# ProDocument__DCDC_2023-12-31.net
KiCad netlist of a schematic drawn in EasyEDA Pro
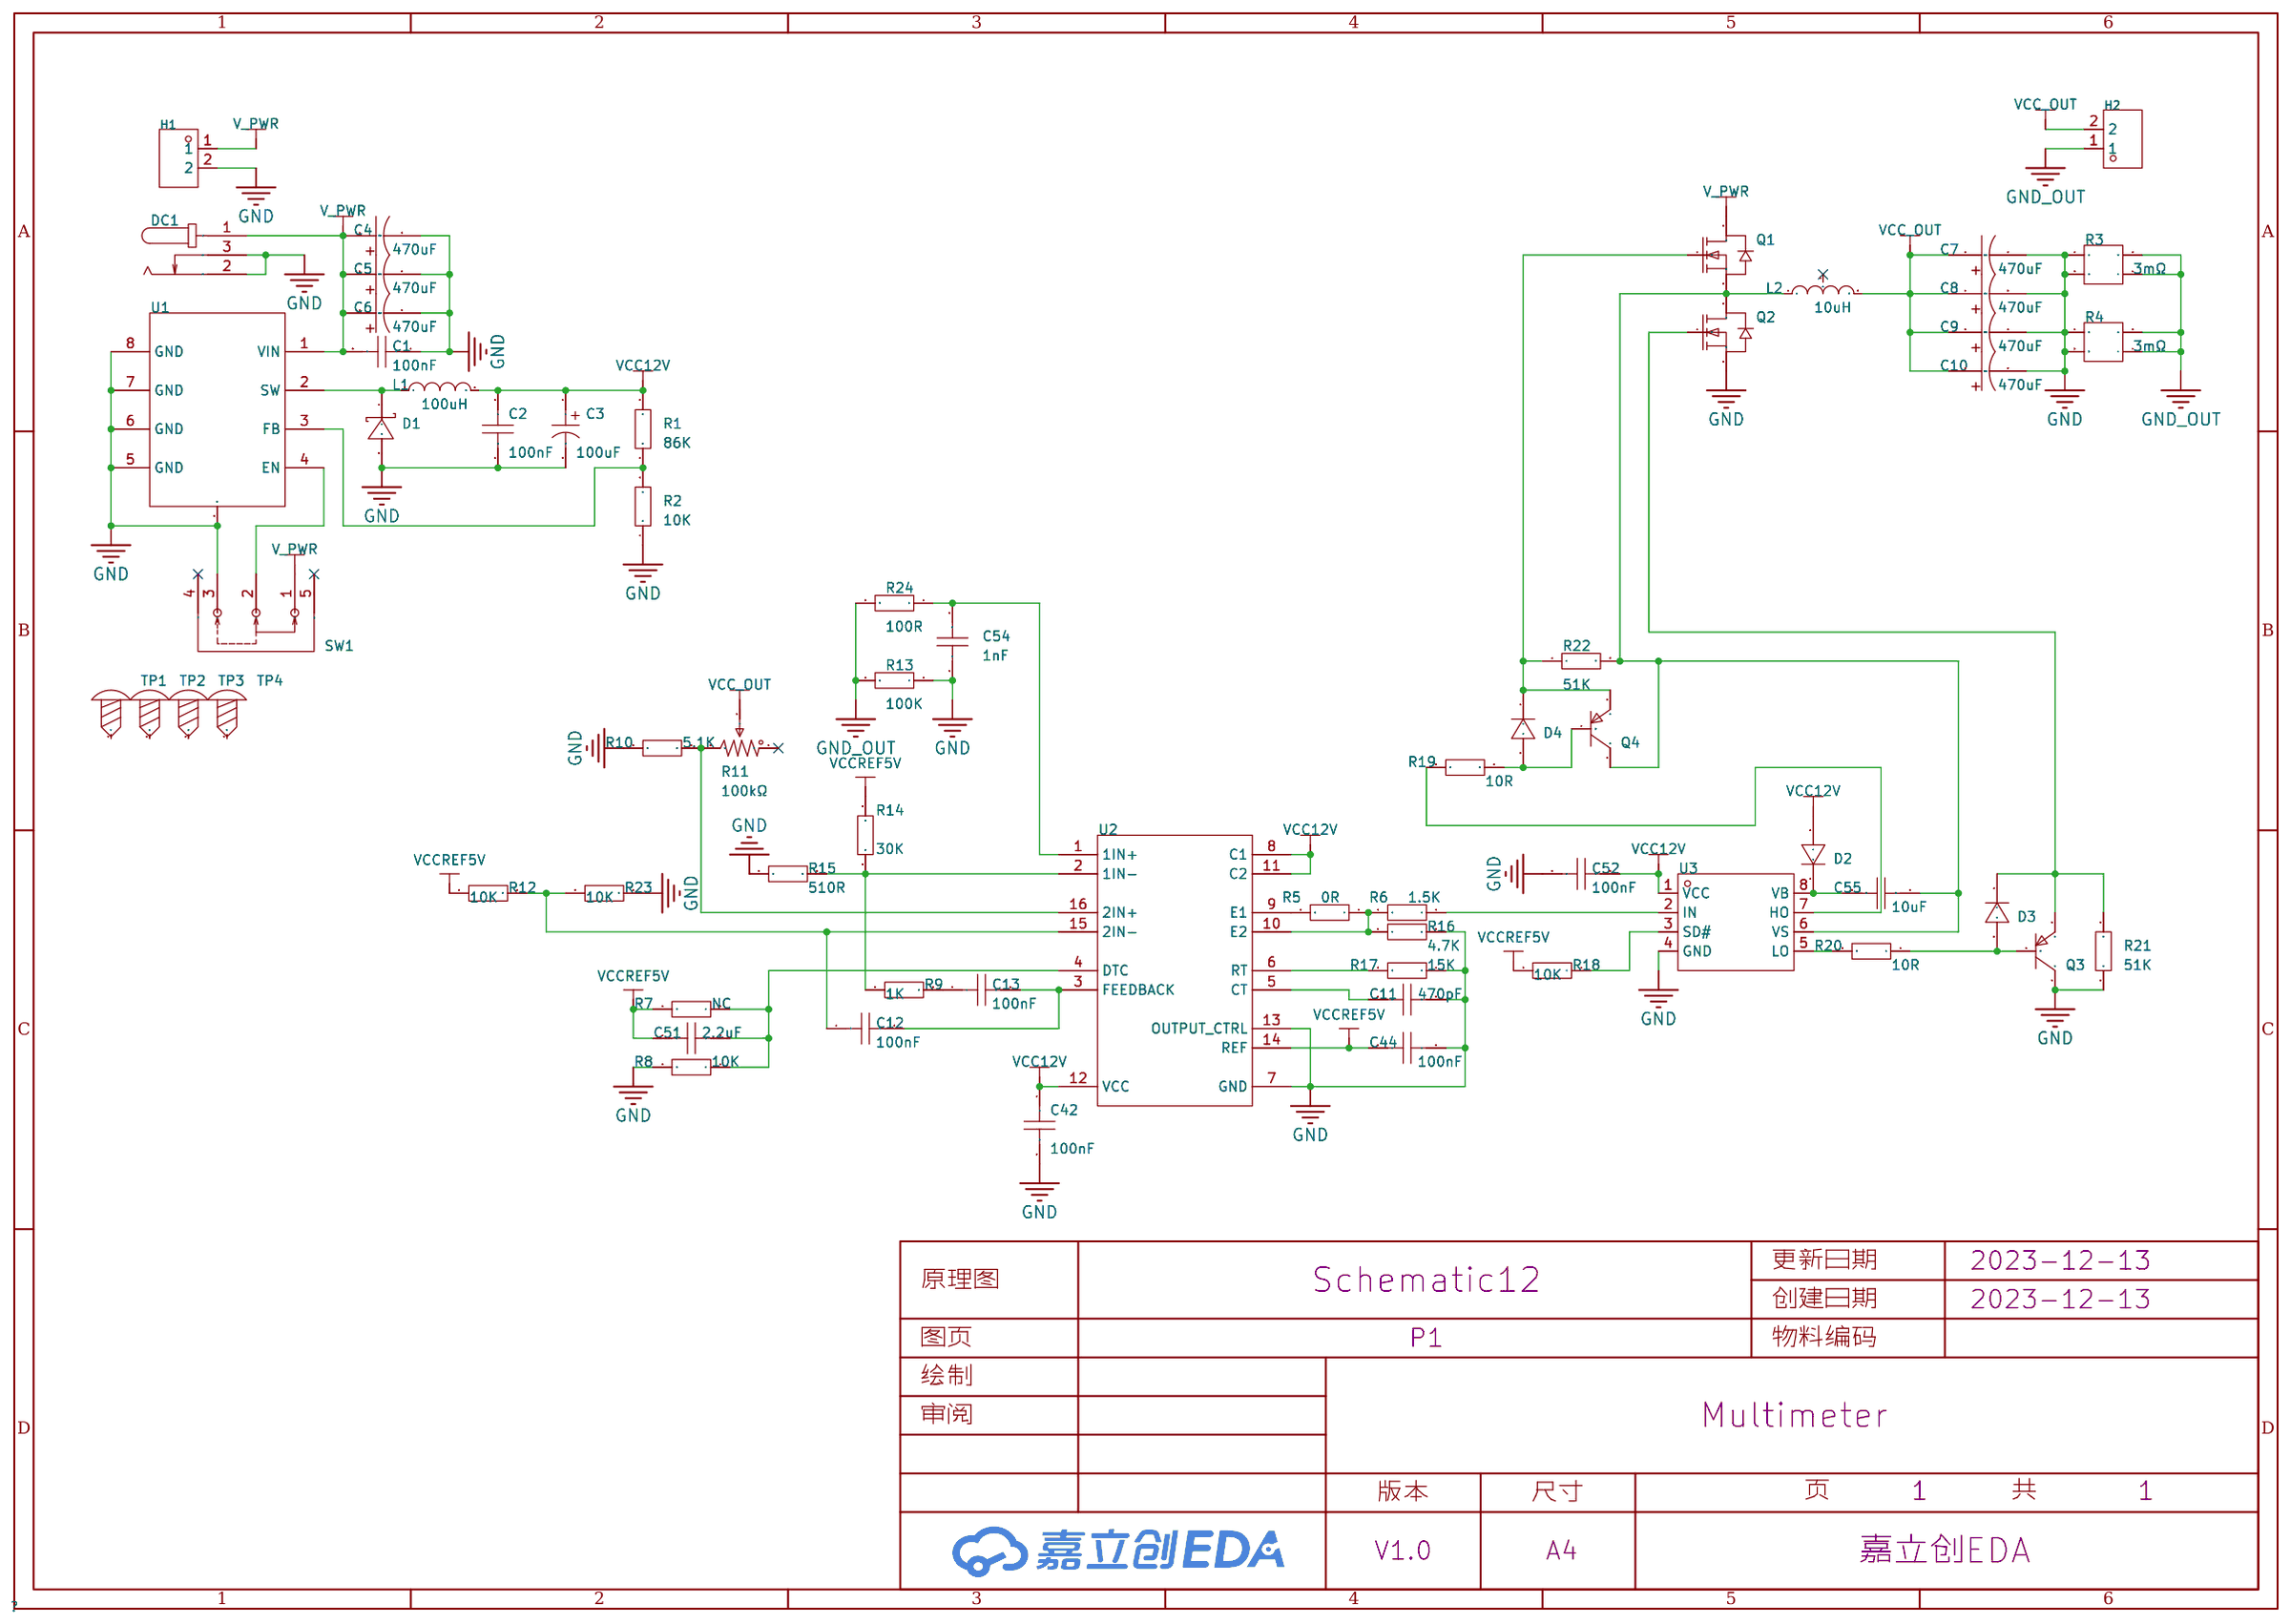
[diagram p0: schematic sheet]

(export (version "E")
  (design (tool "Eeschema 10.0.6"))
  (components
    (comp (ref "C1")
      (value "100nF")
      (footprint "easyedapro:C0603")
      (libsource (lib "easyedapro") (part "CapAcitance"))
    )
    (comp (ref "C2")
      (value "100nF")
      (footprint "easyedapro:C0603")
      (libsource (lib "easyedapro") (part "CapAcitance"))
    )
    (comp (ref "C3")
      (value "100uF")
      (footprint "easyedapro:CAP-SMD_BD6.3-L6.6-W6.6-LS7.6-FD-1")
      (description "容值:100uF;精度:±20%;额定电压:35V;纹波电流:230mA@120Hz;等效串联电阻:600mΩ@100kHz;")
      (fields
        (field (name "Manufacturer Part") "RVE100UF35V67RV0072")
        (field (name "Manufacturer") "KNSCHA(科尼盛)")
      )
      (libsource (lib "easyedapro") (part "RVE100UF35V67RV0072"))
    )
    (comp (ref "C4")
      (value "470uF")
      (footprint "easyedapro:CAP-TH_BD16.0-P7.50-D1.2-FD")
      (description "容值:470uF;精度:±20%;额定电压:100V;纹波电流:-;等效串联电阻:-;")
      (fields (field (name "Manufacturer Part") "ERE1KM471L25OT") (field (name "Manufacturer") "AISHI(艾华集团)"))
      (libsource (lib "easyedapro") (part "ERE1KM471L25OT"))
    )
    (comp (ref "C5")
      (value "470uF")
      (footprint "easyedapro:CAP-TH_BD16.0-P7.50-D1.2-FD")
      (description "容值:470uF;精度:±20%;额定电压:100V;纹波电流:-;等效串联电阻:-;")
      (fields (field (name "Manufacturer Part") "ERE1KM471L25OT") (field (name "Manufacturer") "AISHI(艾华集团)"))
      (libsource (lib "easyedapro") (part "ERE1KM471L25OT"))
    )
    (comp (ref "C6")
      (value "470uF")
      (footprint "easyedapro:CAP-TH_BD16.0-P7.50-D1.2-FD")
      (description "容值:470uF;精度:±20%;额定电压:100V;纹波电流:-;等效串联电阻:-;")
      (fields (field (name "Manufacturer Part") "ERE1KM471L25OT") (field (name "Manufacturer") "AISHI(艾华集团)"))
      (libsource (lib "easyedapro") (part "ERE1KM471L25OT"))
    )
    (comp (ref "C7")
      (value "470uF")
      (footprint "easyedapro:CAP-TH_BD16.0-P7.50-D1.2-FD")
      (description "容值:470uF;精度:±20%;额定电压:100V;纹波电流:-;等效串联电阻:-;")
      (fields (field (name "Manufacturer Part") "ERE1KM471L25OT") (field (name "Manufacturer") "AISHI(艾华集团)"))
      (libsource (lib "easyedapro") (part "ERE1KM471L25OT"))
    )
    (comp (ref "C8")
      (value "470uF")
      (footprint "easyedapro:CAP-TH_BD16.0-P7.50-D1.2-FD")
      (description "容值:470uF;精度:±20%;额定电压:100V;纹波电流:-;等效串联电阻:-;")
      (fields (field (name "Manufacturer Part") "ERE1KM471L25OT") (field (name "Manufacturer") "AISHI(艾华集团)"))
      (libsource (lib "easyedapro") (part "ERE1KM471L25OT"))
    )
    (comp (ref "C9")
      (value "470uF")
      (footprint "easyedapro:CAP-TH_BD16.0-P7.50-D1.2-FD")
      (description "容值:470uF;精度:±20%;额定电压:100V;纹波电流:-;等效串联电阻:-;")
      (fields (field (name "Manufacturer Part") "ERE1KM471L25OT") (field (name "Manufacturer") "AISHI(艾华集团)"))
      (libsource (lib "easyedapro") (part "ERE1KM471L25OT"))
    )
    (comp (ref "C10")
      (value "470uF")
      (footprint "easyedapro:CAP-TH_BD16.0-P7.50-D1.2-FD")
      (description "容值:470uF;精度:±20%;额定电压:100V;纹波电流:-;等效串联电阻:-;")
      (fields (field (name "Manufacturer Part") "ERE1KM471L25OT") (field (name "Manufacturer") "AISHI(艾华集团)"))
      (libsource (lib "easyedapro") (part "ERE1KM471L25OT"))
    )
    (comp (ref "C11")
      (value "470pF")
      (footprint "easyedapro:C0603")
      (libsource (lib "easyedapro") (part "CapAcitance"))
    )
    (comp (ref "C12")
      (value "100nF")
      (footprint "easyedapro:C0603")
      (libsource (lib "easyedapro") (part "CapAcitance"))
    )
    (comp (ref "C13")
      (value "100nF")
      (footprint "easyedapro:C0603")
      (libsource (lib "easyedapro") (part "CapAcitance"))
    )
    (comp (ref "C42")
      (value "100nF")
      (footprint "easyedapro:C0603")
      (libsource (lib "easyedapro") (part "CapAcitance"))
    )
    (comp (ref "C44")
      (value "100nF")
      (footprint "easyedapro:C0603")
      (libsource (lib "easyedapro") (part "CapAcitance"))
    )
    (comp (ref "C51")
      (value "2.2uF")
      (footprint "easyedapro:C0603")
      (libsource (lib "easyedapro") (part "CapAcitance"))
    )
    (comp (ref "C52")
      (value "100nF")
      (footprint "easyedapro:C0603")
      (libsource (lib "easyedapro") (part "CapAcitance"))
    )
    (comp (ref "C54")
      (value "1nF")
      (footprint "easyedapro:C0603")
      (libsource (lib "easyedapro") (part "CapAcitance"))
    )
    (comp (ref "C55")
      (value "10uF")
      (footprint "easyedapro:C0603")
      (description "容值:100nF;精度:±10%;额定电压:50V;材质(温度系数):X7R;")
      (fields
        (field (name "Manufacturer Part") "CC0603KRX7R9BB104")
        (field (name "Manufacturer") "YAGEO(国巨)")
      )
      (libsource (lib "easyedapro") (part "CC0603KRX7R9BB104"))
    )
    (comp (ref "D1")
      (value "SS210")
      (footprint "easyedapro:SMA_L4.3-W2.6-LS5.2-RD")
      (description "直流反向耐压(Vr):100V;平均整流电流(Io):2A;正向压降(Vf):850mV@2A;")
      (fields (field (name "Manufacturer") "MDD"))
      (libsource (lib "easyedapro") (part "SS210"))
    )
    (comp (ref "D2")
      (value "1N4148W")
      (footprint "easyedapro:SOD-123_L2.8-W1.8-LS3.7-RD")
      (fields (field (name "Manufacturer") "CJ(江苏长电/长晶)"))
      (libsource (lib "easyedapro") (part "1N4148W T4"))
    )
    (comp (ref "D3")
      (value "1N4148W")
      (footprint "easyedapro:SOD-123_L2.8-W1.8-LS3.7-RD")
      (fields (field (name "Manufacturer") "CJ(江苏长电/长晶)"))
      (libsource (lib "easyedapro") (part "1N4148W T4"))
    )
    (comp (ref "D4")
      (value "1N4148W")
      (footprint "easyedapro:SOD-123_L2.8-W1.8-LS3.7-RD")
      (fields (field (name "Manufacturer") "CJ(江苏长电/长晶)"))
      (libsource (lib "easyedapro") (part "1N4148W T4"))
    )
    (comp (ref "DC1")
      (value "DC-005-20A")
      (footprint "easyedapro:DC-IN-TH_DC-005-20A")
      (description "触点内径:2mm;触点外径:6.4mm;额定电流:500mA;额定电压:30V;")
      (fields (field (name "Manufacturer") "韩国韩荣"))
      (libsource (lib "easyedapro") (part "DC-005-20A_C136744"))
    )
    (comp (ref "H1")
      (value "DBT50G-9.5-2P")
      (footprint "easyedapro:CONN-TH_2P-P9.50_DBT50G-9.5-2P")
      (fields (field (name "Manufacturer") "DIBO(地博电气)"))
      (libsource (lib "easyedapro") (part "DBT50G-9.5-2P"))
    )
    (comp (ref "H2")
      (value "DBT50G-9.5-2P")
      (footprint "easyedapro:CONN-TH_2P-P9.50_DBT50G-9.5-2P")
      (fields (field (name "Manufacturer") "DIBO(地博电气)"))
      (libsource (lib "easyedapro") (part "DBT50G-9.5-2P"))
    )
    (comp (ref "L1")
      (value "100uH")
      (footprint "easyedapro:IND-SMD_L7.1-W6.6")
      (description "电感值:100uH;精度:±20%;额定电流:1.5A;饱和电流(Isat):2A;")
      (fields (field (name "Manufacturer Part") "SMMS0650-101M") (field (name "Manufacturer") "SXN(顺翔诺)"))
      (libsource (lib "easyedapro") (part "SMMS0650-101M"))
    )
    (comp (ref "L2")
      (value "10uH")
      (footprint "easyedapro:IND-SMD_3P-L27.9-W19.7-P10.43-LS27.9-BL-A")
      (description "电感值:10uH;精度:±20%;额定电流:30A;类型:-;饱和电流(Isat):32.1A;")
      (fields (field (name "Manufacturer Part") "FC-SE2918-100M-28A") (field (name "Manufacturer") "FC(方成)"))
      (libsource (lib "easyedapro") (part "FC-SE2918-100M-28A"))
    )
    (comp (ref "Q1")
      (value "NCEP01T18T")
      (footprint "easyedapro:PG-TO247-3_L15.9-W5.2-P5.44-L")
      (fields (field (name "Manufacturer") "NCE(无锡新洁能)"))
      (libsource (lib "easyedapro") (part "NCEP01T18T"))
    )
    (comp (ref "Q2")
      (value "NCEP01T18T")
      (footprint "easyedapro:PG-TO247-3_L15.9-W5.2-P5.44-L")
      (fields (field (name "Manufacturer") "NCE(无锡新洁能)"))
      (libsource (lib "easyedapro") (part "NCEP01T18T"))
    )
    (comp (ref "Q3")
      (value "SS8550 Y2")
      (footprint "easyedapro:SOT-23-3_L2.9-W1.3-P1.90-LS2.4-BR")
      (description "晶体管类型:PNP;集电极电流(Ic):1.5A;集射极击穿电压(Vceo):25V;功率(Pd):300mW;直流电流增益(hFE@Ic,Vce):200@100mA,1V;")
      (fields (field (name "Manufacturer") "CJ(江苏长电/长晶)"))
      (libsource (lib "easyedapro") (part "SS8550_C8542"))
    )
    (comp (ref "Q4")
      (value "SS8550 Y2")
      (footprint "easyedapro:SOT-23-3_L2.9-W1.3-P1.90-LS2.4-BR")
      (description "晶体管类型:PNP;集电极电流(Ic):1.5A;集射极击穿电压(Vceo):25V;功率(Pd):300mW;直流电流增益(hFE@Ic,Vce):200@100mA,1V;")
      (fields (field (name "Manufacturer") "CJ(江苏长电/长晶)"))
      (libsource (lib "easyedapro") (part "SS8550_C8542"))
    )
    (comp (ref "R1") (value "86K") (footprint "easyedapro:R0603") (libsource (lib "easyedapro") (part "电阻")))
    (comp (ref "R2") (value "10K") (footprint "easyedapro:R0603") (libsource (lib "easyedapro") (part "电阻")))
    (comp (ref "R3")
      (value "3mΩ")
      (footprint "easyedapro:RES-TH_4P-L8.3-W5.3-P3.10-BL")
      (description "阻值:3mΩ;精度:±1%;功率:5W;")
      (fields
        (field (name "Manufacturer Part") "HOBH3820-5W-3mR-1%")
        (field (name "Manufacturer") "Milliohm(毫欧)")
      )
      (libsource (lib "easyedapro") (part "HOBH3820-5W-3MR-1%"))
    )
    (comp (ref "R4")
      (value "3mΩ")
      (footprint "easyedapro:RES-TH_4P-L8.3-W5.3-P3.10-BL")
      (description "阻值:3mΩ;精度:±1%;功率:5W;")
      (fields
        (field (name "Manufacturer Part") "HOBH3820-5W-3mR-1%")
        (field (name "Manufacturer") "Milliohm(毫欧)")
      )
      (libsource (lib "easyedapro") (part "HOBH3820-5W-3MR-1%"))
    )
    (comp (ref "R5") (value "0R") (footprint "easyedapro:R0603") (libsource (lib "easyedapro") (part "电阻")))
    (comp (ref "R6") (value "1.5K") (footprint "easyedapro:R0603") (libsource (lib "easyedapro") (part "电阻")))
    (comp (ref "R7") (value "NC") (footprint "easyedapro:R0603") (libsource (lib "easyedapro") (part "电阻")))
    (comp (ref "R8") (value "10K") (footprint "easyedapro:R0603") (libsource (lib "easyedapro") (part "电阻")))
    (comp (ref "R9") (value "1K") (footprint "easyedapro:R0603") (libsource (lib "easyedapro") (part "电阻")))
    (comp (ref "R10")
      (value "5.1K")
      (footprint "easyedapro:R0603")
      (libsource (lib "easyedapro") (part "电阻"))
    )
    (comp (ref "R11")
      (value "100kΩ")
      (footprint "easyedapro:RES-ADJ-TH_3362P")
      (description "阻值:100kΩ;精度:±10%;")
      (fields (field (name "Manufacturer Part") "3362P-1-104") (field (name "Manufacturer") "BOCHEN(博晨)"))
      (libsource (lib "easyedapro") (part "3362P-1-104_C118966"))
    )
    (comp (ref "R12") (value "10K") (footprint "easyedapro:R0603") (libsource (lib "easyedapro") (part "电阻")))
    (comp (ref "R13")
      (value "100K")
      (footprint "easyedapro:R0603")
      (libsource (lib "easyedapro") (part "电阻"))
    )
    (comp (ref "R14") (value "30K") (footprint "easyedapro:R0603") (libsource (lib "easyedapro") (part "电阻")))
    (comp (ref "R15")
      (value "510R")
      (footprint "easyedapro:R0603")
      (libsource (lib "easyedapro") (part "电阻"))
    )
    (comp (ref "R16")
      (value "4.7K")
      (footprint "easyedapro:R0603")
      (libsource (lib "easyedapro") (part "电阻"))
    )
    (comp (ref "R17") (value "15K") (footprint "easyedapro:R0603") (libsource (lib "easyedapro") (part "电阻")))
    (comp (ref "R18") (value "10K") (footprint "easyedapro:R0603") (libsource (lib "easyedapro") (part "电阻")))
    (comp (ref "R19") (value "10R") (footprint "easyedapro:R0603") (libsource (lib "easyedapro") (part "电阻")))
    (comp (ref "R20") (value "10R") (footprint "easyedapro:R0603") (libsource (lib "easyedapro") (part "电阻")))
    (comp (ref "R21") (value "51K") (footprint "easyedapro:R0603") (libsource (lib "easyedapro") (part "电阻")))
    (comp (ref "R22") (value "51K") (footprint "easyedapro:R0603") (libsource (lib "easyedapro") (part "电阻")))
    (comp (ref "R23") (value "10K") (footprint "easyedapro:R0603") (libsource (lib "easyedapro") (part "电阻")))
    (comp (ref "R24")
      (value "100R")
      (footprint "easyedapro:R0603")
      (libsource (lib "easyedapro") (part "电阻"))
    )
    (comp (ref "SW1")
      (value "SK12D07VG4")
      (footprint "easyedapro:SW-TH_SK12D07VG4")
      (description "电路结构:单刀双掷;安装方式:卧插;额定电流(DC):500mA;额定电压(DC):50V;额定电流(AC):-;额定电压(AC):-;机械寿命:5千次;")
      (fields (field (name "Manufacturer") "SHOU HAN(首韩)"))
      (libsource (lib "easyedapro") (part "SK12D07VG4"))
    )
    (comp (ref "TP1") (value "~") (footprint "easyedapro:M3螺丝") (libsource (lib "easyedapro") (part "螺丝孔")))
    (comp (ref "TP2") (value "~") (footprint "easyedapro:M3螺丝") (libsource (lib "easyedapro") (part "螺丝孔")))
    (comp (ref "TP3") (value "~") (footprint "easyedapro:M3螺丝") (libsource (lib "easyedapro") (part "螺丝孔")))
    (comp (ref "TP4") (value "~") (footprint "easyedapro:M3螺丝") (libsource (lib "easyedapro") (part "螺丝孔")))
    (comp (ref "U1")
      (value "XL7005A")
      (footprint "easyedapro:SOIC-8_L4.9-W3.9-P1.27-LS6.0-BL-EP3.1-1")
      (description "功能类型:降压型;同步整流:-;输出通道数:-;拓扑结构:-;输入电压:-;输出电流(最大值):-;开关频率:-;")
      (fields (field (name "Manufacturer") "XLSEMI(芯龙)"))
      (libsource (lib "easyedapro") (part "XL7005A"))
    )
    (comp (ref "U2")
      (value "TL494CDR")
      (footprint "easyedapro:SOIC-16_L9.9-W3.9-P1.27-LS6.0-BL")
      (description "TL494 脉冲宽度调制 (Pwm) 控制电路")
      (fields (field (name "Manufacturer") "TI(德州仪器)"))
      (libsource (lib "easyedapro") (part "TL494CDR"))
    )
    (comp (ref "U3")
      (value "EG2104")
      (footprint "easyedapro:SOP-8_L5.0-W4.0-P1.27-LS6.2-BL")
      (description "高性价比, 600V，半桥式Nmos预驱动器")
      (fields (field (name "Manufacturer") "EG(屹晶微)"))
      (libsource (lib "easyedapro") (part "EG2104"))
    )
  )
  (nets
    (net (code "1") (name "GND") (class "Default")
      (node (ref "C1") (pin "1") (pinfunction "1_1") (pintype "input"))
      (node (ref "C10") (pin "2") (pinfunction "2_2") (pintype "input"))
      (node (ref "C11") (pin "2") (pinfunction "2_2") (pintype "input"))
      (node (ref "C2") (pin "1") (pinfunction "1_1") (pintype "input"))
      (node (ref "C3") (pin "2") (pinfunction "2_2") (pintype "input"))
      (node (ref "C4") (pin "2") (pinfunction "2_2") (pintype "input"))
      (node (ref "C42") (pin "2") (pinfunction "2_2") (pintype "input"))
      (node (ref "C44") (pin "2") (pinfunction "2_2") (pintype "input"))
      (node (ref "C5") (pin "2") (pinfunction "2_2") (pintype "input"))
      (node (ref "C52") (pin "1") (pinfunction "1_1") (pintype "input"))
      (node (ref "C54") (pin "1") (pinfunction "1_1") (pintype "input"))
      (node (ref "C6") (pin "2") (pinfunction "2_2") (pintype "input"))
      (node (ref "C7") (pin "2") (pinfunction "2_2") (pintype "input"))
      (node (ref "C8") (pin "2") (pinfunction "2_2") (pintype "input"))
      (node (ref "C9") (pin "2") (pinfunction "2_2") (pintype "input"))
      (node (ref "D1") (pin "2") (pinfunction "A_2") (pintype "input"))
      (node (ref "DC1") (pin "2") (pinfunction "2_2") (pintype "input"))
      (node (ref "DC1") (pin "3") (pinfunction "3_3") (pintype "input"))
      (node (ref "H1") (pin "2") (pinfunction "2_2") (pintype "input"))
      (node (ref "Q2") (pin "3") (pinfunction "S_3") (pintype "input"))
      (node (ref "Q3") (pin "3") (pinfunction "C_3") (pintype "unspecified"))
      (node (ref "R10") (pin "2") (pinfunction "2_2") (pintype "input"))
      (node (ref "R13") (pin "1") (pinfunction "1_1") (pintype "input"))
      (node (ref "R15") (pin "2") (pinfunction "2_2") (pintype "input"))
      (node (ref "R16") (pin "1") (pinfunction "1_1") (pintype "input"))
      (node (ref "R17") (pin "1") (pinfunction "1_1") (pintype "input"))
      (node (ref "R2") (pin "1") (pinfunction "1_1") (pintype "input"))
      (node (ref "R21") (pin "2") (pinfunction "2_2") (pintype "input"))
      (node (ref "R23") (pin "1") (pinfunction "1_1") (pintype "input"))
      (node (ref "R3") (pin "1") (pinfunction "1_1") (pintype "input"))
      (node (ref "R3") (pin "3") (pinfunction "3_3") (pintype "input"))
      (node (ref "R4") (pin "1") (pinfunction "1_1") (pintype "input"))
      (node (ref "R4") (pin "3") (pinfunction "3_3") (pintype "input"))
      (node (ref "R8") (pin "2") (pinfunction "2_2") (pintype "input"))
      (node (ref "SW1") (pin "3") (pinfunction "3_3") (pintype "unspecified"))
      (node (ref "U1") (pin "5") (pinfunction "GND_5") (pintype "input"))
      (node (ref "U1") (pin "6") (pinfunction "GND_6") (pintype "input"))
      (node (ref "U1") (pin "7") (pinfunction "GND_7") (pintype "input"))
      (node (ref "U1") (pin "8") (pinfunction "GND_8") (pintype "input"))
      (node (ref "U1") (pin "9") (pinfunction "9_9") (pintype "input"))
      (node (ref "U2") (pin "13") (pinfunction "OUTPUT_CTRL_13") (pintype "input"))
      (node (ref "U2") (pin "7") (pinfunction "GND_7") (pintype "input"))
      (node (ref "U3") (pin "4") (pinfunction "GND_4") (pintype "unspecified"))
    )
    (net (code "2") (name "GND_OUT") (class "Default")
      (node (ref "H2") (pin "1") (pinfunction "1_1") (pintype "input"))
      (node (ref "R13") (pin "2") (pinfunction "2_2") (pintype "input"))
      (node (ref "R24") (pin "2") (pinfunction "2_2") (pintype "input"))
      (node (ref "R3") (pin "2") (pinfunction "2_2") (pintype "input"))
      (node (ref "R3") (pin "4") (pinfunction "4_4") (pintype "input"))
      (node (ref "R4") (pin "2") (pinfunction "2_2") (pintype "input"))
      (node (ref "R4") (pin "4") (pinfunction "4_4") (pintype "input"))
    )
    (net (code "3") (name "Net-(C13-Pad1)") (class "Default")
      (node (ref "C13") (pin "1") (pinfunction "1_1") (pintype "input"))
      (node (ref "R9") (pin "1") (pinfunction "1_1") (pintype "input"))
    )
    (net (code "4") (name "Net-(D1-K)") (class "Default")
      (node (ref "D1") (pin "1") (pinfunction "K_1") (pintype "input"))
      (node (ref "L1") (pin "1") (pinfunction "1_1") (pintype "input"))
      (node (ref "U1") (pin "2") (pinfunction "SW_2") (pintype "input"))
    )
    (net (code "5") (name "Net-(D2-K)") (class "Default")
      (node (ref "C55") (pin "2") (pinfunction "2_2") (pintype "input"))
      (node (ref "D2") (pin "1") (pinfunction "K_1") (pintype "input"))
      (node (ref "U3") (pin "8") (pinfunction "VB_8") (pintype "unspecified"))
    )
    (net (code "6") (name "Net-(D3-A)") (class "Default")
      (node (ref "D3") (pin "2") (pinfunction "A_2") (pintype "input"))
      (node (ref "Q3") (pin "1") (pinfunction "B_1") (pintype "unspecified"))
      (node (ref "R20") (pin "1") (pinfunction "1_1") (pintype "input"))
    )
    (net (code "7") (name "Net-(D3-K)") (class "Default")
      (node (ref "D3") (pin "1") (pinfunction "K_1") (pintype "input"))
      (node (ref "Q2") (pin "1") (pinfunction "G_1") (pintype "input"))
      (node (ref "Q3") (pin "2") (pinfunction "E_2") (pintype "unspecified"))
      (node (ref "R21") (pin "1") (pinfunction "1_1") (pintype "input"))
    )
    (net (code "8") (name "Net-(D4-A)") (class "Default")
      (node (ref "D4") (pin "2") (pinfunction "A_2") (pintype "input"))
      (node (ref "Q4") (pin "1") (pinfunction "B_1") (pintype "unspecified"))
      (node (ref "R19") (pin "1") (pinfunction "1_1") (pintype "input"))
    )
    (net (code "9") (name "Net-(D4-K)") (class "Default")
      (node (ref "D4") (pin "1") (pinfunction "K_1") (pintype "input"))
      (node (ref "Q1") (pin "1") (pinfunction "G_1") (pintype "input"))
      (node (ref "Q4") (pin "2") (pinfunction "E_2") (pintype "unspecified"))
      (node (ref "R22") (pin "1") (pinfunction "1_1") (pintype "input"))
    )
    (net (code "10") (name "Net-(Q1-S)") (class "Default")
      (node (ref "C55") (pin "1") (pinfunction "1_1") (pintype "input"))
      (node (ref "L2") (pin "1") (pinfunction "1_1") (pintype "unspecified"))
      (node (ref "Q1") (pin "3") (pinfunction "S_3") (pintype "input"))
      (node (ref "Q2") (pin "2") (pinfunction "D_2") (pintype "input"))
      (node (ref "Q4") (pin "3") (pinfunction "C_3") (pintype "unspecified"))
      (node (ref "R22") (pin "2") (pinfunction "2_2") (pintype "input"))
      (node (ref "U3") (pin "6") (pinfunction "VS_6") (pintype "unspecified"))
    )
    (net (code "11") (name "Net-(U1-EN)") (class "Default")
      (node (ref "SW1") (pin "2") (pinfunction "2_2") (pintype "unspecified"))
      (node (ref "U1") (pin "4") (pinfunction "EN_4") (pintype "input"))
    )
    (net (code "12") (name "Net-(U1-FB)") (class "Default")
      (node (ref "R1") (pin "1") (pinfunction "1_1") (pintype "input"))
      (node (ref "R2") (pin "2") (pinfunction "2_2") (pintype "input"))
      (node (ref "U1") (pin "3") (pinfunction "FB_3") (pintype "input"))
    )
    (net (code "13") (name "Net-(U2-1IN+)") (class "Default")
      (node (ref "C54") (pin "2") (pinfunction "2_2") (pintype "input"))
      (node (ref "R24") (pin "1") (pinfunction "1_1") (pintype "input"))
      (node (ref "U2") (pin "1") (pinfunction "1IN+_1") (pintype "input"))
    )
    (net (code "14") (name "Net-(U2-1IN-)") (class "Default")
      (node (ref "R14") (pin "2") (pinfunction "2_2") (pintype "input"))
      (node (ref "R15") (pin "1") (pinfunction "1_1") (pintype "input"))
      (node (ref "R9") (pin "2") (pinfunction "2_2") (pintype "input"))
      (node (ref "U2") (pin "2") (pinfunction "1IN-_2") (pintype "input"))
    )
    (net (code "15") (name "Net-(U2-2IN+)") (class "Default")
      (node (ref "R10") (pin "1") (pinfunction "1_1") (pintype "input"))
      (node (ref "R11") (pin "3") (pinfunction "3_3") (pintype "input"))
      (node (ref "U2") (pin "16") (pinfunction "2IN+_16") (pintype "input"))
    )
    (net (code "16") (name "Net-(U2-2IN-)") (class "Default")
      (node (ref "C12") (pin "1") (pinfunction "1_1") (pintype "input"))
      (node (ref "R12") (pin "1") (pinfunction "1_1") (pintype "input"))
      (node (ref "R23") (pin "2") (pinfunction "2_2") (pintype "input"))
      (node (ref "U2") (pin "15") (pinfunction "2IN-_15") (pintype "input"))
    )
    (net (code "17") (name "Net-(U2-CT)") (class "Default")
      (node (ref "C11") (pin "1") (pinfunction "1_1") (pintype "input"))
      (node (ref "U2") (pin "5") (pinfunction "CT_5") (pintype "input"))
    )
    (net (code "18") (name "Net-(U2-DTC)") (class "Default")
      (node (ref "C51") (pin "2") (pinfunction "2_2") (pintype "input"))
      (node (ref "R7") (pin "1") (pinfunction "1_1") (pintype "input"))
      (node (ref "R8") (pin "1") (pinfunction "1_1") (pintype "input"))
      (node (ref "U2") (pin "4") (pinfunction "DTC_4") (pintype "input"))
    )
    (net (code "19") (name "Net-(U2-E1)") (class "Default")
      (node (ref "R5") (pin "2") (pinfunction "2_2") (pintype "input"))
      (node (ref "U2") (pin "9") (pinfunction "E1_9") (pintype "input"))
    )
    (net (code "20") (name "Net-(U2-E2)") (class "Default")
      (node (ref "R16") (pin "2") (pinfunction "2_2") (pintype "input"))
      (node (ref "R5") (pin "1") (pinfunction "1_1") (pintype "input"))
      (node (ref "R6") (pin "2") (pinfunction "2_2") (pintype "input"))
      (node (ref "U2") (pin "10") (pinfunction "E2_10") (pintype "input"))
    )
    (net (code "21") (name "Net-(U2-FEEDBACK)") (class "Default")
      (node (ref "C12") (pin "2") (pinfunction "2_2") (pintype "input"))
      (node (ref "C13") (pin "2") (pinfunction "2_2") (pintype "input"))
      (node (ref "U2") (pin "3") (pinfunction "FEEDBACK_3") (pintype "input"))
    )
    (net (code "22") (name "Net-(U2-RT)") (class "Default")
      (node (ref "R17") (pin "2") (pinfunction "2_2") (pintype "input"))
      (node (ref "U2") (pin "6") (pinfunction "RT_6") (pintype "input"))
    )
    (net (code "23") (name "Net-(U3-HO)") (class "Default")
      (node (ref "R19") (pin "2") (pinfunction "2_2") (pintype "input"))
      (node (ref "U3") (pin "7") (pinfunction "HO_7") (pintype "unspecified"))
    )
    (net (code "24") (name "Net-(U3-IN)") (class "Default")
      (node (ref "R6") (pin "1") (pinfunction "1_1") (pintype "input"))
      (node (ref "U3") (pin "2") (pinfunction "IN_2") (pintype "unspecified"))
    )
    (net (code "25") (name "Net-(U3-LO)") (class "Default")
      (node (ref "R20") (pin "2") (pinfunction "2_2") (pintype "input"))
      (node (ref "U3") (pin "5") (pinfunction "LO_5") (pintype "unspecified"))
    )
    (net (code "26") (name "Net-(U3-SD#)") (class "Default")
      (node (ref "R18") (pin "1") (pinfunction "1_1") (pintype "input"))
      (node (ref "U3") (pin "3") (pinfunction "SD#_3") (pintype "unspecified"))
    )
    (net (code "27") (name "VCC12V") (class "Default")
      (node (ref "C2") (pin "2") (pinfunction "2_2") (pintype "input"))
      (node (ref "C3") (pin "1") (pinfunction "1_1") (pintype "input"))
      (node (ref "C42") (pin "1") (pinfunction "1_1") (pintype "input"))
      (node (ref "C52") (pin "2") (pinfunction "2_2") (pintype "input"))
      (node (ref "D2") (pin "2") (pinfunction "A_2") (pintype "input"))
      (node (ref "L1") (pin "2") (pinfunction "2_2") (pintype "input"))
      (node (ref "R1") (pin "2") (pinfunction "2_2") (pintype "input"))
      (node (ref "U2") (pin "11") (pinfunction "C2_11") (pintype "input"))
      (node (ref "U2") (pin "12") (pinfunction "VCC_12") (pintype "input"))
      (node (ref "U2") (pin "8") (pinfunction "C1_8") (pintype "input"))
      (node (ref "U3") (pin "1") (pinfunction "VCC_1") (pintype "unspecified"))
    )
    (net (code "28") (name "VCCREF5V") (class "Default")
      (node (ref "C44") (pin "1") (pinfunction "1_1") (pintype "input"))
      (node (ref "C51") (pin "1") (pinfunction "1_1") (pintype "input"))
      (node (ref "R12") (pin "2") (pinfunction "2_2") (pintype "input"))
      (node (ref "R14") (pin "1") (pinfunction "1_1") (pintype "input"))
      (node (ref "R18") (pin "2") (pinfunction "2_2") (pintype "input"))
      (node (ref "R7") (pin "2") (pinfunction "2_2") (pintype "input"))
      (node (ref "U2") (pin "14") (pinfunction "REF_14") (pintype "output"))
    )
    (net (code "29") (name "VCC_OUT") (class "Default")
      (node (ref "C10") (pin "1") (pinfunction "1_1") (pintype "input"))
      (node (ref "C7") (pin "1") (pinfunction "1_1") (pintype "input"))
      (node (ref "C8") (pin "1") (pinfunction "1_1") (pintype "input"))
      (node (ref "C9") (pin "1") (pinfunction "1_1") (pintype "input"))
      (node (ref "H2") (pin "2") (pinfunction "2_2") (pintype "input"))
      (node (ref "L2") (pin "2") (pinfunction "2_2") (pintype "unspecified"))
      (node (ref "R11") (pin "2") (pinfunction "2_2") (pintype "input"))
    )
    (net (code "30") (name "V_PWR") (class "Default")
      (node (ref "C1") (pin "2") (pinfunction "2_2") (pintype "input"))
      (node (ref "C4") (pin "1") (pinfunction "1_1") (pintype "input"))
      (node (ref "C5") (pin "1") (pinfunction "1_1") (pintype "input"))
      (node (ref "C6") (pin "1") (pinfunction "1_1") (pintype "input"))
      (node (ref "DC1") (pin "1") (pinfunction "1_1") (pintype "input"))
      (node (ref "H1") (pin "1") (pinfunction "1_1") (pintype "input"))
      (node (ref "Q1") (pin "2") (pinfunction "D_2") (pintype "input"))
      (node (ref "SW1") (pin "1") (pinfunction "1_1") (pintype "unspecified"))
      (node (ref "U1") (pin "1") (pinfunction "VIN_1") (pintype "input"))
    )
    (net (code "31") (name "unconnected-(L2-Pad3)") (class "Default")
      (node (ref "L2") (pin "3") (pinfunction "3_3") (pintype "unspecified+no_connect"))
    )
    (net (code "32") (name "unconnected-(R11-Pad1)") (class "Default")
      (node (ref "R11") (pin "1") (pinfunction "1_1") (pintype "input+no_connect"))
    )
    (net (code "33") (name "unconnected-(SW1-Pad4)") (class "Default")
      (node (ref "SW1") (pin "4") (pinfunction "4_4") (pintype "unspecified+no_connect"))
    )
    (net (code "34") (name "unconnected-(SW1-Pad5)") (class "Default")
      (node (ref "SW1") (pin "5") (pinfunction "5_5") (pintype "unspecified+no_connect"))
    )
    (net (code "35") (name "unconnected-(TP1-Pad1)") (class "Default")
      (node (ref "TP1") (pin "1") (pinfunction "1_1") (pintype "input"))
    )
    (net (code "36") (name "unconnected-(TP2-Pad1)") (class "Default")
      (node (ref "TP2") (pin "1") (pinfunction "1_1") (pintype "input"))
    )
    (net (code "37") (name "unconnected-(TP3-Pad1)") (class "Default")
      (node (ref "TP3") (pin "1") (pinfunction "1_1") (pintype "input"))
    )
    (net (code "38") (name "unconnected-(TP4-Pad1)") (class "Default")
      (node (ref "TP4") (pin "1") (pinfunction "1_1") (pintype "input"))
    )
  )
)
